# LVDS_IFC_DDS.net
KiCad netlist of a schematic drawn in Altium Designer
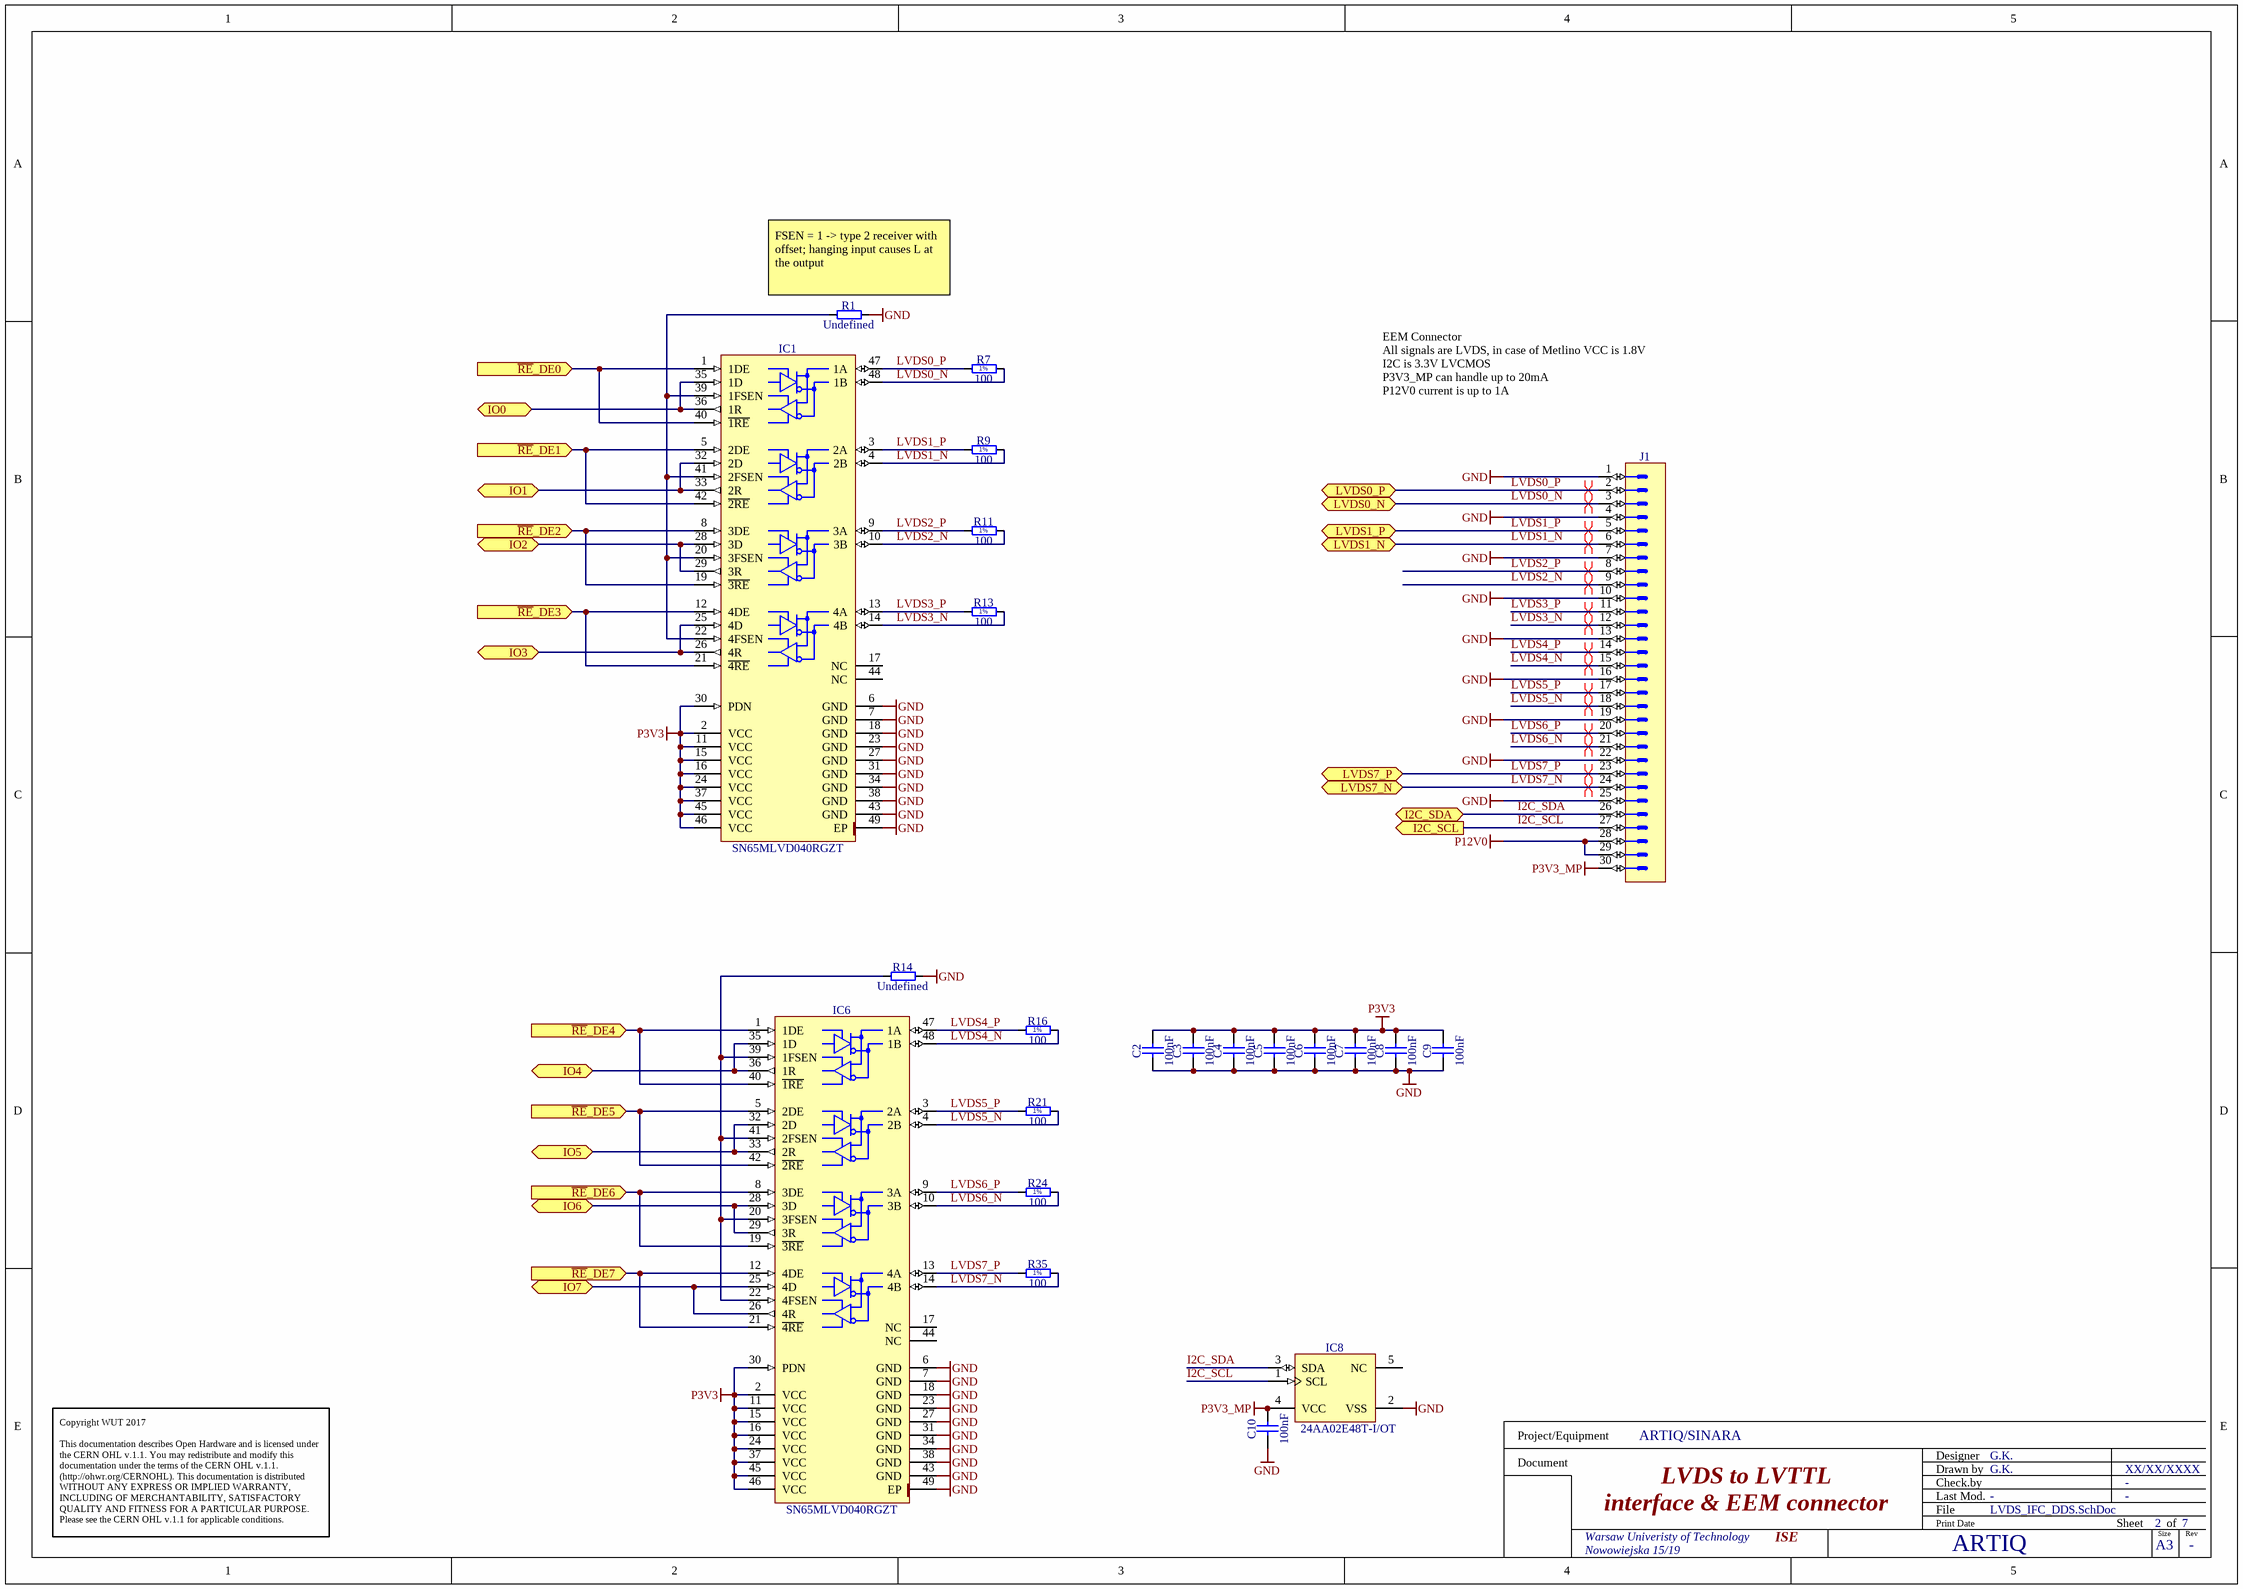
[diagram p0: LVDS_IFC_DDS.SchDoc]

(export (version "E")
  (design (tool "Eeschema 10.0.6"))
  (components
    (comp (ref "C2")
      (value "100nF")
      (footprint "CAPC1005X55N")
      (description "Non-polarised capacitor")
      (fields
        (field (name "PART NUMBER") "CC0402_100NF_16V_10%_X5R")
        (field (name "VOLTAGE") "16V")
        (field (name "AUTHOR") "CERN DEM JLC")
      )
      (libsource (lib "Capacitors") (part "Capacitor - non polarized"))
    )
    (comp (ref "C3")
      (value "100nF")
      (footprint "CAPC1005X55N")
      (description "Non-polarised capacitor")
      (fields
        (field (name "PART NUMBER") "CC0402_100NF_16V_10%_X5R")
        (field (name "VOLTAGE") "16V")
        (field (name "AUTHOR") "CERN DEM JLC")
      )
      (libsource (lib "Capacitors") (part "Capacitor - non polarized"))
    )
    (comp (ref "C4")
      (value "100nF")
      (footprint "CAPC1005X55N")
      (description "Non-polarised capacitor")
      (fields
        (field (name "PART NUMBER") "CC0402_100NF_16V_10%_X5R")
        (field (name "VOLTAGE") "16V")
        (field (name "AUTHOR") "CERN DEM JLC")
      )
      (libsource (lib "Capacitors") (part "Capacitor - non polarized"))
    )
    (comp (ref "C5")
      (value "100nF")
      (footprint "CAPC1005X55N")
      (description "Non-polarised capacitor")
      (fields
        (field (name "PART NUMBER") "CC0402_100NF_16V_10%_X5R")
        (field (name "VOLTAGE") "16V")
        (field (name "AUTHOR") "CERN DEM JLC")
      )
      (libsource (lib "Capacitors") (part "Capacitor - non polarized"))
    )
    (comp (ref "C6")
      (value "100nF")
      (footprint "CAPC1005X55N")
      (description "Non-polarised capacitor")
      (fields
        (field (name "PART NUMBER") "CC0402_100NF_16V_10%_X5R")
        (field (name "VOLTAGE") "16V")
        (field (name "AUTHOR") "CERN DEM JLC")
      )
      (libsource (lib "Capacitors") (part "Capacitor - non polarized"))
    )
    (comp (ref "C7")
      (value "100nF")
      (footprint "CAPC1005X55N")
      (description "Non-polarised capacitor")
      (fields
        (field (name "PART NUMBER") "CC0402_100NF_16V_10%_X5R")
        (field (name "VOLTAGE") "16V")
        (field (name "AUTHOR") "CERN DEM JLC")
      )
      (libsource (lib "Capacitors") (part "Capacitor - non polarized"))
    )
    (comp (ref "C8")
      (value "100nF")
      (footprint "CAPC1005X55N")
      (description "Non-polarised capacitor")
      (fields
        (field (name "PART NUMBER") "CC0402_100NF_16V_10%_X5R")
        (field (name "VOLTAGE") "16V")
        (field (name "AUTHOR") "CERN DEM JLC")
      )
      (libsource (lib "Capacitors") (part "Capacitor - non polarized"))
    )
    (comp (ref "C9")
      (value "100nF")
      (footprint "CAPC1005X55N")
      (description "Non-polarised capacitor")
      (fields
        (field (name "PART NUMBER") "CC0402_100NF_16V_10%_X5R")
        (field (name "VOLTAGE") "16V")
        (field (name "AUTHOR") "CERN DEM JLC")
      )
      (libsource (lib "Capacitors") (part "Capacitor - non polarized"))
    )
    (comp (ref "C10")
      (value "100nF")
      (footprint "CAPC1005X55N")
      (description "Non-polarised capacitor")
      (fields
        (field (name "PART NUMBER") "CC0402_100NF_16V_10%_X5R")
        (field (name "VOLTAGE") "16V")
        (field (name "AUTHOR") "CERN DEM JLC")
      )
      (libsource (lib "Capacitors") (part "Capacitor - non polarized"))
    )
    (comp (ref "IC1")
      (value "SN65MLVD040RGZT")
      (footprint "QFN50P700X700X100-49N-S420")
      (description "4-Channel Half-Duplex M-LVDS Line Transceiver")
      (fields (field (name "MANUFACTURER") "TEXAS INSTRUMENTS") (field (name "AUTHOR") "CERN DEM JLC"))
      (libsource (lib "ICs And Semiconductors") (part "SN65MLVD040"))
    )
    (comp (ref "IC6")
      (value "SN65MLVD040RGZT")
      (footprint "QFN50P700X700X100-49N-S420")
      (description "4-Channel Half-Duplex M-LVDS Line Transceiver")
      (fields (field (name "MANUFACTURER") "TEXAS INSTRUMENTS") (field (name "AUTHOR") "CERN DEM JLC"))
      (libsource (lib "ICs And Semiconductors") (part "SN65MLVD040"))
    )
    (comp (ref "IC8")
      (value "24AA02E48T-I/OT")
      (footprint "SOT95P280X145-5N")
      (description "1.7V-5.5V, 2K I2C Serial EEPROM With EUI-48 Node Identity")
      (fields (field (name "MANUFACTURER") "MICROCHIP TECHNOLOGY") (field (name "AUTHOR") "CERN DEM MR"))
      (libsource (lib "ICs And Semiconductors") (part "24AA02E48T-I/OT"))
    )
    (comp (ref "J1")
      (value "~")
      (footprint "3M_N2530-6002RB")
      (description "Connector 30 Male")
      (fields
        (field (name "PART NUMBER") "3M_N2530-6002RB")
        (field (name "MANUFACTURER") "3M")
        (field (name "AUTHOR") "CERN DEM JLC")
      )
      (libsource (lib "Connectors") (part "Connector 30 Male"))
    )
    (comp (ref "R1")
      (value "Undefined")
      (footprint "RESC1005X40N")
      (description "Resistor")
      (fields (field (name "PART NUMBER") "R0402_NO-VALUE") (field (name "AUTHOR") "CERN DEM JLC"))
      (libsource (lib "Resistors") (part "Resistor"))
    )
    (comp (ref "R7")
      (value "100")
      (footprint "RESC1005X40N")
      (description "Resistor - 1%")
      (fields
        (field (name "PART NUMBER") "R0402_100R_1%_0.1W_100PPM")
        (field (name "POWER") "0.1W")
        (field (name "AUTHOR") "CERN DEM JLC")
      )
      (libsource (lib "Resistors") (part "Resistor - 1%"))
    )
    (comp (ref "R9")
      (value "100")
      (footprint "RESC1005X40N")
      (description "Resistor - 1%")
      (fields
        (field (name "PART NUMBER") "R0402_100R_1%_0.1W_100PPM")
        (field (name "POWER") "0.1W")
        (field (name "AUTHOR") "CERN DEM JLC")
      )
      (libsource (lib "Resistors") (part "Resistor - 1%"))
    )
    (comp (ref "R11")
      (value "100")
      (footprint "RESC1005X40N")
      (description "Resistor - 1%")
      (fields
        (field (name "PART NUMBER") "R0402_100R_1%_0.1W_100PPM")
        (field (name "POWER") "0.1W")
        (field (name "AUTHOR") "CERN DEM JLC")
      )
      (libsource (lib "Resistors") (part "Resistor - 1%"))
    )
    (comp (ref "R13")
      (value "100")
      (footprint "RESC1005X40N")
      (description "Resistor - 1%")
      (fields
        (field (name "PART NUMBER") "R0402_100R_1%_0.1W_100PPM")
        (field (name "POWER") "0.1W")
        (field (name "AUTHOR") "CERN DEM JLC")
      )
      (libsource (lib "Resistors") (part "Resistor - 1%"))
    )
    (comp (ref "R14")
      (value "Undefined")
      (footprint "RESC1005X40N")
      (description "Resistor")
      (fields (field (name "PART NUMBER") "R0402_NO-VALUE") (field (name "AUTHOR") "CERN DEM JLC"))
      (libsource (lib "Resistors") (part "Resistor"))
    )
    (comp (ref "R16")
      (value "100")
      (footprint "RESC1005X40N")
      (description "Resistor - 1%")
      (fields
        (field (name "PART NUMBER") "R0402_100R_1%_0.1W_100PPM")
        (field (name "POWER") "0.1W")
        (field (name "AUTHOR") "CERN DEM JLC")
      )
      (libsource (lib "Resistors") (part "Resistor - 1%"))
    )
    (comp (ref "R21")
      (value "100")
      (footprint "RESC1005X40N")
      (description "Resistor - 1%")
      (fields
        (field (name "PART NUMBER") "R0402_100R_1%_0.1W_100PPM")
        (field (name "POWER") "0.1W")
        (field (name "AUTHOR") "CERN DEM JLC")
      )
      (libsource (lib "Resistors") (part "Resistor - 1%"))
    )
    (comp (ref "R24")
      (value "100")
      (footprint "RESC1005X40N")
      (description "Resistor - 1%")
      (fields
        (field (name "PART NUMBER") "R0402_100R_1%_0.1W_100PPM")
        (field (name "POWER") "0.1W")
        (field (name "AUTHOR") "CERN DEM JLC")
      )
      (libsource (lib "Resistors") (part "Resistor - 1%"))
    )
    (comp (ref "R35")
      (value "100")
      (footprint "RESC1005X40N")
      (description "Resistor - 1%")
      (fields
        (field (name "PART NUMBER") "R0402_100R_1%_0.1W_100PPM")
        (field (name "POWER") "0.1W")
        (field (name "AUTHOR") "CERN DEM JLC")
      )
      (libsource (lib "Resistors") (part "Resistor - 1%"))
    )
  )
  (nets
    (net (code "1") (name "/I2C_SCL") (class "Default")
      (node (ref "IC8") (pin "1") (pinfunction "SCL_1") (pintype "input"))
      (node (ref "J1") (pin "27") (pinfunction "27_27") (pintype "bidirectional"))
    )
    (net (code "2") (name "/I2C_SDA") (class "Default")
      (node (ref "IC8") (pin "3") (pinfunction "SDA_3") (pintype "bidirectional"))
      (node (ref "J1") (pin "26") (pinfunction "26_26") (pintype "bidirectional"))
    )
    (net (code "3") (name "/IO0") (class "Default")
      (node (ref "IC1") (pin "35") (pinfunction "1D_35") (pintype "input"))
      (node (ref "IC1") (pin "36") (pinfunction "1R_36") (pintype "output"))
    )
    (net (code "4") (name "/IO1") (class "Default")
      (node (ref "IC1") (pin "32") (pinfunction "2D_32") (pintype "input"))
      (node (ref "IC1") (pin "33") (pinfunction "2R_33") (pintype "output"))
    )
    (net (code "5") (name "/IO2") (class "Default")
      (node (ref "IC1") (pin "28") (pinfunction "3D_28") (pintype "input"))
      (node (ref "IC1") (pin "29") (pinfunction "3R_29") (pintype "output"))
    )
    (net (code "6") (name "/IO3") (class "Default")
      (node (ref "IC1") (pin "25") (pinfunction "4D_25") (pintype "input"))
      (node (ref "IC1") (pin "26") (pinfunction "4R_26") (pintype "output"))
    )
    (net (code "7") (name "/IO4") (class "Default")
      (node (ref "IC6") (pin "35") (pinfunction "1D_35") (pintype "input"))
      (node (ref "IC6") (pin "36") (pinfunction "1R_36") (pintype "output"))
    )
    (net (code "8") (name "/IO5") (class "Default")
      (node (ref "IC6") (pin "32") (pinfunction "2D_32") (pintype "input"))
      (node (ref "IC6") (pin "33") (pinfunction "2R_33") (pintype "output"))
    )
    (net (code "9") (name "/IO6") (class "Default")
      (node (ref "IC6") (pin "28") (pinfunction "3D_28") (pintype "input"))
      (node (ref "IC6") (pin "29") (pinfunction "3R_29") (pintype "output"))
    )
    (net (code "10") (name "/IO7") (class "Default")
      (node (ref "IC6") (pin "25") (pinfunction "4D_25") (pintype "input"))
      (node (ref "IC6") (pin "26") (pinfunction "4R_26") (pintype "output"))
    )
    (net (code "11") (name "/LVDS0_N") (class "Default")
      (node (ref "IC1") (pin "48") (pinfunction "1B_48") (pintype "bidirectional"))
      (node (ref "J1") (pin "3") (pinfunction "3_3") (pintype "bidirectional"))
      (node (ref "R7") (pin "2") (pinfunction "2_2") (pintype "passive"))
    )
    (net (code "12") (name "/LVDS0_P") (class "Default")
      (node (ref "IC1") (pin "47") (pinfunction "1A_47") (pintype "bidirectional"))
      (node (ref "J1") (pin "2") (pinfunction "2_2") (pintype "bidirectional"))
      (node (ref "R7") (pin "1") (pinfunction "1_1") (pintype "passive"))
    )
    (net (code "13") (name "/LVDS1_N") (class "Default")
      (node (ref "IC1") (pin "4") (pinfunction "2B_4") (pintype "bidirectional"))
      (node (ref "J1") (pin "6") (pinfunction "6_6") (pintype "bidirectional"))
      (node (ref "R9") (pin "2") (pinfunction "2_2") (pintype "passive"))
    )
    (net (code "14") (name "/LVDS1_P") (class "Default")
      (node (ref "IC1") (pin "3") (pinfunction "2A_3") (pintype "bidirectional"))
      (node (ref "J1") (pin "5") (pinfunction "5_5") (pintype "bidirectional"))
      (node (ref "R9") (pin "1") (pinfunction "1_1") (pintype "passive"))
    )
    (net (code "15") (name "/LVDS2_N") (class "Default")
      (node (ref "IC1") (pin "10") (pinfunction "3B_10") (pintype "bidirectional"))
      (node (ref "J1") (pin "9") (pinfunction "9_9") (pintype "bidirectional"))
      (node (ref "R11") (pin "2") (pinfunction "2_2") (pintype "passive"))
    )
    (net (code "16") (name "/LVDS2_P") (class "Default")
      (node (ref "IC1") (pin "9") (pinfunction "3A_9") (pintype "bidirectional"))
      (node (ref "J1") (pin "8") (pinfunction "8_8") (pintype "bidirectional"))
      (node (ref "R11") (pin "1") (pinfunction "1_1") (pintype "passive"))
    )
    (net (code "17") (name "/LVDS3_N") (class "Default")
      (node (ref "IC1") (pin "14") (pinfunction "4B_14") (pintype "bidirectional"))
      (node (ref "J1") (pin "12") (pinfunction "12_12") (pintype "bidirectional"))
      (node (ref "R13") (pin "2") (pinfunction "2_2") (pintype "passive"))
    )
    (net (code "18") (name "/LVDS3_P") (class "Default")
      (node (ref "IC1") (pin "13") (pinfunction "4A_13") (pintype "bidirectional"))
      (node (ref "J1") (pin "11") (pinfunction "11_11") (pintype "bidirectional"))
      (node (ref "R13") (pin "1") (pinfunction "1_1") (pintype "passive"))
    )
    (net (code "19") (name "/LVDS4_N") (class "Default")
      (node (ref "IC6") (pin "48") (pinfunction "1B_48") (pintype "bidirectional"))
      (node (ref "J1") (pin "15") (pinfunction "15_15") (pintype "bidirectional"))
      (node (ref "R16") (pin "2") (pinfunction "2_2") (pintype "passive"))
    )
    (net (code "20") (name "/LVDS4_P") (class "Default")
      (node (ref "IC6") (pin "47") (pinfunction "1A_47") (pintype "bidirectional"))
      (node (ref "J1") (pin "14") (pinfunction "14_14") (pintype "bidirectional"))
      (node (ref "R16") (pin "1") (pinfunction "1_1") (pintype "passive"))
    )
    (net (code "21") (name "/LVDS5_N") (class "Default")
      (node (ref "IC6") (pin "4") (pinfunction "2B_4") (pintype "bidirectional"))
      (node (ref "J1") (pin "18") (pinfunction "18_18") (pintype "bidirectional"))
      (node (ref "R21") (pin "2") (pinfunction "2_2") (pintype "passive"))
    )
    (net (code "22") (name "/LVDS5_P") (class "Default")
      (node (ref "IC6") (pin "3") (pinfunction "2A_3") (pintype "bidirectional"))
      (node (ref "J1") (pin "17") (pinfunction "17_17") (pintype "bidirectional"))
      (node (ref "R21") (pin "1") (pinfunction "1_1") (pintype "passive"))
    )
    (net (code "23") (name "/LVDS6_N") (class "Default")
      (node (ref "IC6") (pin "10") (pinfunction "3B_10") (pintype "bidirectional"))
      (node (ref "J1") (pin "21") (pinfunction "21_21") (pintype "bidirectional"))
      (node (ref "R24") (pin "2") (pinfunction "2_2") (pintype "passive"))
    )
    (net (code "24") (name "/LVDS6_P") (class "Default")
      (node (ref "IC6") (pin "9") (pinfunction "3A_9") (pintype "bidirectional"))
      (node (ref "J1") (pin "20") (pinfunction "20_20") (pintype "bidirectional"))
      (node (ref "R24") (pin "1") (pinfunction "1_1") (pintype "passive"))
    )
    (net (code "25") (name "/LVDS7_N") (class "Default")
      (node (ref "IC6") (pin "14") (pinfunction "4B_14") (pintype "bidirectional"))
      (node (ref "J1") (pin "24") (pinfunction "24_24") (pintype "bidirectional"))
      (node (ref "R35") (pin "2") (pinfunction "2_2") (pintype "passive"))
    )
    (net (code "26") (name "/LVDS7_P") (class "Default")
      (node (ref "IC6") (pin "13") (pinfunction "4A_13") (pintype "bidirectional"))
      (node (ref "J1") (pin "23") (pinfunction "23_23") (pintype "bidirectional"))
      (node (ref "R35") (pin "1") (pinfunction "1_1") (pintype "passive"))
    )
    (net (code "27") (name "/~{RE}_DE0") (class "Default")
      (node (ref "IC1") (pin "1") (pinfunction "1DE_1") (pintype "input"))
      (node (ref "IC1") (pin "40") (pinfunction "~{1RE}_40") (pintype "input"))
    )
    (net (code "28") (name "/~{RE}_DE1") (class "Default")
      (node (ref "IC1") (pin "42") (pinfunction "~{2RE}_42") (pintype "input"))
      (node (ref "IC1") (pin "5") (pinfunction "2DE_5") (pintype "input"))
    )
    (net (code "29") (name "/~{RE}_DE2") (class "Default")
      (node (ref "IC1") (pin "19") (pinfunction "~{3RE}_19") (pintype "input"))
      (node (ref "IC1") (pin "8") (pinfunction "3DE_8") (pintype "input"))
    )
    (net (code "30") (name "/~{RE}_DE3") (class "Default")
      (node (ref "IC1") (pin "12") (pinfunction "4DE_12") (pintype "input"))
      (node (ref "IC1") (pin "21") (pinfunction "~{4RE}_21") (pintype "input"))
    )
    (net (code "31") (name "/~{RE}_DE4") (class "Default")
      (node (ref "IC6") (pin "1") (pinfunction "1DE_1") (pintype "input"))
      (node (ref "IC6") (pin "40") (pinfunction "~{1RE}_40") (pintype "input"))
    )
    (net (code "32") (name "/~{RE}_DE5") (class "Default")
      (node (ref "IC6") (pin "42") (pinfunction "~{2RE}_42") (pintype "input"))
      (node (ref "IC6") (pin "5") (pinfunction "2DE_5") (pintype "input"))
    )
    (net (code "33") (name "/~{RE}_DE6") (class "Default")
      (node (ref "IC6") (pin "19") (pinfunction "~{3RE}_19") (pintype "input"))
      (node (ref "IC6") (pin "8") (pinfunction "3DE_8") (pintype "input"))
    )
    (net (code "34") (name "/~{RE}_DE7") (class "Default")
      (node (ref "IC6") (pin "12") (pinfunction "4DE_12") (pintype "input"))
      (node (ref "IC6") (pin "21") (pinfunction "~{4RE}_21") (pintype "input"))
    )
    (net (code "35") (name "GND") (class "Default")
      (node (ref "C10") (pin "1") (pinfunction "1_1") (pintype "passive"))
      (node (ref "C2") (pin "1") (pinfunction "1_1") (pintype "passive"))
      (node (ref "C3") (pin "1") (pinfunction "1_1") (pintype "passive"))
      (node (ref "C4") (pin "1") (pinfunction "1_1") (pintype "passive"))
      (node (ref "C5") (pin "1") (pinfunction "1_1") (pintype "passive"))
      (node (ref "C6") (pin "1") (pinfunction "1_1") (pintype "passive"))
      (node (ref "C7") (pin "1") (pinfunction "1_1") (pintype "passive"))
      (node (ref "C8") (pin "1") (pinfunction "1_1") (pintype "passive"))
      (node (ref "C9") (pin "1") (pinfunction "1_1") (pintype "passive"))
      (node (ref "IC1") (pin "18") (pinfunction "GND_18") (pintype "power_in"))
      (node (ref "IC1") (pin "23") (pinfunction "GND_23") (pintype "power_in"))
      (node (ref "IC1") (pin "27") (pinfunction "GND_27") (pintype "power_in"))
      (node (ref "IC1") (pin "31") (pinfunction "GND_31") (pintype "power_in"))
      (node (ref "IC1") (pin "34") (pinfunction "GND_34") (pintype "power_in"))
      (node (ref "IC1") (pin "38") (pinfunction "GND_38") (pintype "power_in"))
      (node (ref "IC1") (pin "43") (pinfunction "GND_43") (pintype "power_in"))
      (node (ref "IC1") (pin "49") (pinfunction "EP_49") (pintype "power_in"))
      (node (ref "IC1") (pin "6") (pinfunction "GND_6") (pintype "power_in"))
      (node (ref "IC1") (pin "7") (pinfunction "GND_7") (pintype "power_in"))
      (node (ref "IC6") (pin "18") (pinfunction "GND_18") (pintype "power_in"))
      (node (ref "IC6") (pin "23") (pinfunction "GND_23") (pintype "power_in"))
      (node (ref "IC6") (pin "27") (pinfunction "GND_27") (pintype "power_in"))
      (node (ref "IC6") (pin "31") (pinfunction "GND_31") (pintype "power_in"))
      (node (ref "IC6") (pin "34") (pinfunction "GND_34") (pintype "power_in"))
      (node (ref "IC6") (pin "38") (pinfunction "GND_38") (pintype "power_in"))
      (node (ref "IC6") (pin "43") (pinfunction "GND_43") (pintype "power_in"))
      (node (ref "IC6") (pin "49") (pinfunction "EP_49") (pintype "power_in"))
      (node (ref "IC6") (pin "6") (pinfunction "GND_6") (pintype "power_in"))
      (node (ref "IC6") (pin "7") (pinfunction "GND_7") (pintype "power_in"))
      (node (ref "IC8") (pin "2") (pinfunction "VSS_2") (pintype "power_in"))
      (node (ref "J1") (pin "1") (pinfunction "1_1") (pintype "bidirectional"))
      (node (ref "J1") (pin "10") (pinfunction "10_10") (pintype "bidirectional"))
      (node (ref "J1") (pin "13") (pinfunction "13_13") (pintype "bidirectional"))
      (node (ref "J1") (pin "16") (pinfunction "16_16") (pintype "bidirectional"))
      (node (ref "J1") (pin "19") (pinfunction "19_19") (pintype "bidirectional"))
      (node (ref "J1") (pin "22") (pinfunction "22_22") (pintype "bidirectional"))
      (node (ref "J1") (pin "25") (pinfunction "25_25") (pintype "bidirectional"))
      (node (ref "J1") (pin "4") (pinfunction "4_4") (pintype "bidirectional"))
      (node (ref "J1") (pin "7") (pinfunction "7_7") (pintype "bidirectional"))
      (node (ref "R1") (pin "2") (pinfunction "2_2") (pintype "passive"))
      (node (ref "R14") (pin "2") (pinfunction "2_2") (pintype "passive"))
    )
    (net (code "36") (name "Net-(IC1-1FSEN)") (class "Default")
      (node (ref "IC1") (pin "20") (pinfunction "3FSEN_20") (pintype "input"))
      (node (ref "IC1") (pin "22") (pinfunction "4FSEN_22") (pintype "input"))
      (node (ref "IC1") (pin "39") (pinfunction "1FSEN_39") (pintype "input"))
      (node (ref "IC1") (pin "41") (pinfunction "2FSEN_41") (pintype "input"))
      (node (ref "R1") (pin "1") (pinfunction "1_1") (pintype "passive"))
    )
    (net (code "37") (name "Net-(IC6-1FSEN)") (class "Default")
      (node (ref "IC6") (pin "20") (pinfunction "3FSEN_20") (pintype "input"))
      (node (ref "IC6") (pin "22") (pinfunction "4FSEN_22") (pintype "input"))
      (node (ref "IC6") (pin "39") (pinfunction "1FSEN_39") (pintype "input"))
      (node (ref "IC6") (pin "41") (pinfunction "2FSEN_41") (pintype "input"))
      (node (ref "R14") (pin "1") (pinfunction "1_1") (pintype "passive"))
    )
    (net (code "38") (name "P3V3") (class "Default")
      (node (ref "C2") (pin "2") (pinfunction "2_2") (pintype "passive"))
      (node (ref "C3") (pin "2") (pinfunction "2_2") (pintype "passive"))
      (node (ref "C4") (pin "2") (pinfunction "2_2") (pintype "passive"))
      (node (ref "C5") (pin "2") (pinfunction "2_2") (pintype "passive"))
      (node (ref "C6") (pin "2") (pinfunction "2_2") (pintype "passive"))
      (node (ref "C7") (pin "2") (pinfunction "2_2") (pintype "passive"))
      (node (ref "C8") (pin "2") (pinfunction "2_2") (pintype "passive"))
      (node (ref "C9") (pin "2") (pinfunction "2_2") (pintype "passive"))
      (node (ref "IC1") (pin "11") (pinfunction "VCC_11") (pintype "power_in"))
      (node (ref "IC1") (pin "15") (pinfunction "VCC_15") (pintype "power_in"))
      (node (ref "IC1") (pin "16") (pinfunction "VCC_16") (pintype "power_in"))
      (node (ref "IC1") (pin "2") (pinfunction "VCC_2") (pintype "power_in"))
      (node (ref "IC1") (pin "24") (pinfunction "VCC_24") (pintype "power_in"))
      (node (ref "IC1") (pin "30") (pinfunction "PDN_30") (pintype "input"))
      (node (ref "IC1") (pin "37") (pinfunction "VCC_37") (pintype "power_in"))
      (node (ref "IC1") (pin "45") (pinfunction "VCC_45") (pintype "power_in"))
      (node (ref "IC1") (pin "46") (pinfunction "VCC_46") (pintype "power_in"))
      (node (ref "IC6") (pin "11") (pinfunction "VCC_11") (pintype "power_in"))
      (node (ref "IC6") (pin "15") (pinfunction "VCC_15") (pintype "power_in"))
      (node (ref "IC6") (pin "16") (pinfunction "VCC_16") (pintype "power_in"))
      (node (ref "IC6") (pin "2") (pinfunction "VCC_2") (pintype "power_in"))
      (node (ref "IC6") (pin "24") (pinfunction "VCC_24") (pintype "power_in"))
      (node (ref "IC6") (pin "30") (pinfunction "PDN_30") (pintype "input"))
      (node (ref "IC6") (pin "37") (pinfunction "VCC_37") (pintype "power_in"))
      (node (ref "IC6") (pin "45") (pinfunction "VCC_45") (pintype "power_in"))
      (node (ref "IC6") (pin "46") (pinfunction "VCC_46") (pintype "power_in"))
    )
    (net (code "39") (name "P3V3_MP") (class "Default")
      (node (ref "C10") (pin "2") (pinfunction "2_2") (pintype "passive"))
      (node (ref "IC8") (pin "4") (pinfunction "VCC_4") (pintype "power_in"))
      (node (ref "J1") (pin "30") (pinfunction "30_30") (pintype "bidirectional"))
    )
    (net (code "40") (name "P12V0") (class "Default")
      (node (ref "J1") (pin "28") (pinfunction "28_28") (pintype "bidirectional"))
      (node (ref "J1") (pin "29") (pinfunction "29_29") (pintype "bidirectional"))
    )
    (net (code "41") (name "unconnected-(IC1-NC-Pad17)") (class "Default")
      (node (ref "IC1") (pin "17") (pinfunction "NC_17") (pintype "passive"))
    )
    (net (code "42") (name "unconnected-(IC1-NC-Pad44)") (class "Default")
      (node (ref "IC1") (pin "44") (pinfunction "NC_44") (pintype "passive"))
    )
    (net (code "43") (name "unconnected-(IC6-NC-Pad17)") (class "Default")
      (node (ref "IC6") (pin "17") (pinfunction "NC_17") (pintype "passive"))
    )
    (net (code "44") (name "unconnected-(IC6-NC-Pad44)") (class "Default")
      (node (ref "IC6") (pin "44") (pinfunction "NC_44") (pintype "passive"))
    )
    (net (code "45") (name "unconnected-(IC8-NC-Pad5)") (class "Default")
      (node (ref "IC8") (pin "5") (pinfunction "NC_5") (pintype "passive"))
    )
  )
)
